# CRE401.net
KiCad netlist of a schematic drawn in Altium Designer
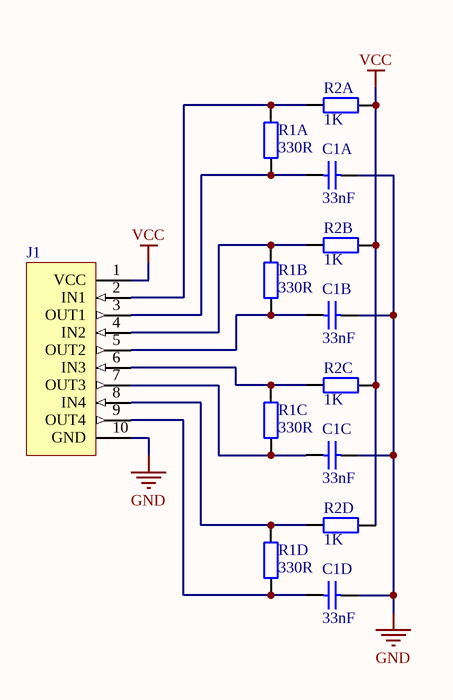
[diagram p0: CRE401.SchDoc]

(export (version "E")
  (design (tool "Eeschema 10.0.6"))
  (components
    (comp (ref "C1A")
      (value "33nF")
      (footprint "CAPC1608N")
      (description "Capacitor (SMD), 0603")
      (fields (field (name "Comment") "Cap0603"))
      (libsource (lib "CRE401") (part "Cap0603"))
    )
    (comp (ref "C1B")
      (value "33nF")
      (footprint "CAPC1608N")
      (description "Capacitor (SMD), 0603")
      (fields (field (name "Comment") "Cap0603"))
      (libsource (lib "CRE401") (part "Cap0603"))
    )
    (comp (ref "C1C")
      (value "33nF")
      (footprint "CAPC1608N")
      (description "Capacitor (SMD), 0603")
      (fields (field (name "Comment") "Cap0603"))
      (libsource (lib "CRE401") (part "Cap0603"))
    )
    (comp (ref "C1D")
      (value "33nF")
      (footprint "CAPC1608N")
      (description "Capacitor (SMD), 0603")
      (fields (field (name "Comment") "Cap0603"))
      (libsource (lib "CRE401") (part "Cap0603"))
    )
    (comp (ref "J1")
      (value "CRE401 HEADER")
      (footprint "HEADER10_SMD_THT")
      (description "10p 0.1\" header, male, right angle or vertical")
      (libsource (lib "CRE401") (part "CRE401 HEADER"))
    )
    (comp (ref "R1A")
      (value "330R")
      (footprint "RESC1608N")
      (description "Resistor (SMD), 0603")
      (fields (field (name "Comment") "Res0603"))
      (libsource (lib "CRE401") (part "Res0603"))
    )
    (comp (ref "R1B")
      (value "330R")
      (footprint "RESC1608N")
      (description "Resistor (SMD), 0603")
      (fields (field (name "Comment") "Res0603"))
      (libsource (lib "CRE401") (part "Res0603"))
    )
    (comp (ref "R1C")
      (value "330R")
      (footprint "RESC1608N")
      (description "Resistor (SMD), 0603")
      (fields (field (name "Comment") "Res0603"))
      (libsource (lib "CRE401") (part "Res0603"))
    )
    (comp (ref "R1D")
      (value "330R")
      (footprint "RESC1608N")
      (description "Resistor (SMD), 0603")
      (fields (field (name "Comment") "Res0603"))
      (libsource (lib "CRE401") (part "Res0603"))
    )
    (comp (ref "R2A")
      (value "1K")
      (footprint "RESC1608N")
      (description "Resistor (SMD), 0603")
      (fields (field (name "Comment") "Res0603"))
      (libsource (lib "") (part "Res0603_1"))
    )
    (comp (ref "R2B")
      (value "1K")
      (footprint "RESC1608N")
      (description "Resistor (SMD), 0603")
      (fields (field (name "Comment") "Res0603"))
      (libsource (lib "") (part "Res0603_1"))
    )
    (comp (ref "R2C")
      (value "1K")
      (footprint "RESC1608N")
      (description "Resistor (SMD), 0603")
      (fields (field (name "Comment") "Res0603"))
      (libsource (lib "") (part "Res0603_1"))
    )
    (comp (ref "R2D")
      (value "1K")
      (footprint "RESC1608N")
      (description "Resistor (SMD), 0603")
      (fields (field (name "Comment") "Res0603"))
      (libsource (lib "") (part "Res0603_1"))
    )
  )
  (nets
    (net (code "1") (name "GND") (class "Default")
      (node (ref "C1A") (pin "2") (pinfunction "2_2") (pintype "passive"))
      (node (ref "C1B") (pin "2") (pinfunction "2_2") (pintype "passive"))
      (node (ref "C1C") (pin "2") (pinfunction "2_2") (pintype "passive"))
      (node (ref "C1D") (pin "2") (pinfunction "2_2") (pintype "passive"))
      (node (ref "J1") (pin "10") (pinfunction "GND_10") (pintype "power_in"))
    )
    (net (code "2") (name "Net-(J1-IN1)") (class "Default")
      (node (ref "J1") (pin "2") (pinfunction "IN1_2") (pintype "input"))
      (node (ref "R1A") (pin "2") (pinfunction "2_2") (pintype "passive"))
      (node (ref "R2A") (pin "1") (pinfunction "1_1") (pintype "passive"))
    )
    (net (code "3") (name "Net-(J1-IN2)") (class "Default")
      (node (ref "J1") (pin "4") (pinfunction "IN2_4") (pintype "input"))
      (node (ref "R1B") (pin "2") (pinfunction "2_2") (pintype "passive"))
      (node (ref "R2B") (pin "1") (pinfunction "1_1") (pintype "passive"))
    )
    (net (code "4") (name "Net-(J1-IN3)") (class "Default")
      (node (ref "J1") (pin "6") (pinfunction "IN3_6") (pintype "input"))
      (node (ref "R1C") (pin "2") (pinfunction "2_2") (pintype "passive"))
      (node (ref "R2C") (pin "1") (pinfunction "1_1") (pintype "passive"))
    )
    (net (code "5") (name "Net-(J1-IN4)") (class "Default")
      (node (ref "J1") (pin "8") (pinfunction "IN4_8") (pintype "input"))
      (node (ref "R1D") (pin "2") (pinfunction "2_2") (pintype "passive"))
      (node (ref "R2D") (pin "1") (pinfunction "1_1") (pintype "passive"))
    )
    (net (code "6") (name "Net-(J1-OUT1)") (class "Default")
      (node (ref "C1A") (pin "1") (pinfunction "1_1") (pintype "passive"))
      (node (ref "J1") (pin "3") (pinfunction "OUT1_3") (pintype "output"))
      (node (ref "R1A") (pin "1") (pinfunction "1_1") (pintype "passive"))
    )
    (net (code "7") (name "Net-(J1-OUT2)") (class "Default")
      (node (ref "C1B") (pin "1") (pinfunction "1_1") (pintype "passive"))
      (node (ref "J1") (pin "5") (pinfunction "OUT2_5") (pintype "output"))
      (node (ref "R1B") (pin "1") (pinfunction "1_1") (pintype "passive"))
    )
    (net (code "8") (name "Net-(J1-OUT3)") (class "Default")
      (node (ref "C1C") (pin "1") (pinfunction "1_1") (pintype "passive"))
      (node (ref "J1") (pin "7") (pinfunction "OUT3_7") (pintype "output"))
      (node (ref "R1C") (pin "1") (pinfunction "1_1") (pintype "passive"))
    )
    (net (code "9") (name "Net-(J1-OUT4)") (class "Default")
      (node (ref "C1D") (pin "1") (pinfunction "1_1") (pintype "passive"))
      (node (ref "J1") (pin "9") (pinfunction "OUT4_9") (pintype "output"))
      (node (ref "R1D") (pin "1") (pinfunction "1_1") (pintype "passive"))
    )
    (net (code "10") (name "VCC") (class "Default")
      (node (ref "J1") (pin "1") (pinfunction "VCC_1") (pintype "power_in"))
      (node (ref "R2A") (pin "2") (pinfunction "2_2") (pintype "passive"))
      (node (ref "R2B") (pin "2") (pinfunction "2_2") (pintype "passive"))
      (node (ref "R2C") (pin "2") (pinfunction "2_2") (pintype "passive"))
      (node (ref "R2D") (pin "2") (pinfunction "2_2") (pintype "passive"))
    )
  )
)
